# SCH_bottomBoard.net
KiCad netlist of a schematic drawn in EasyEDA
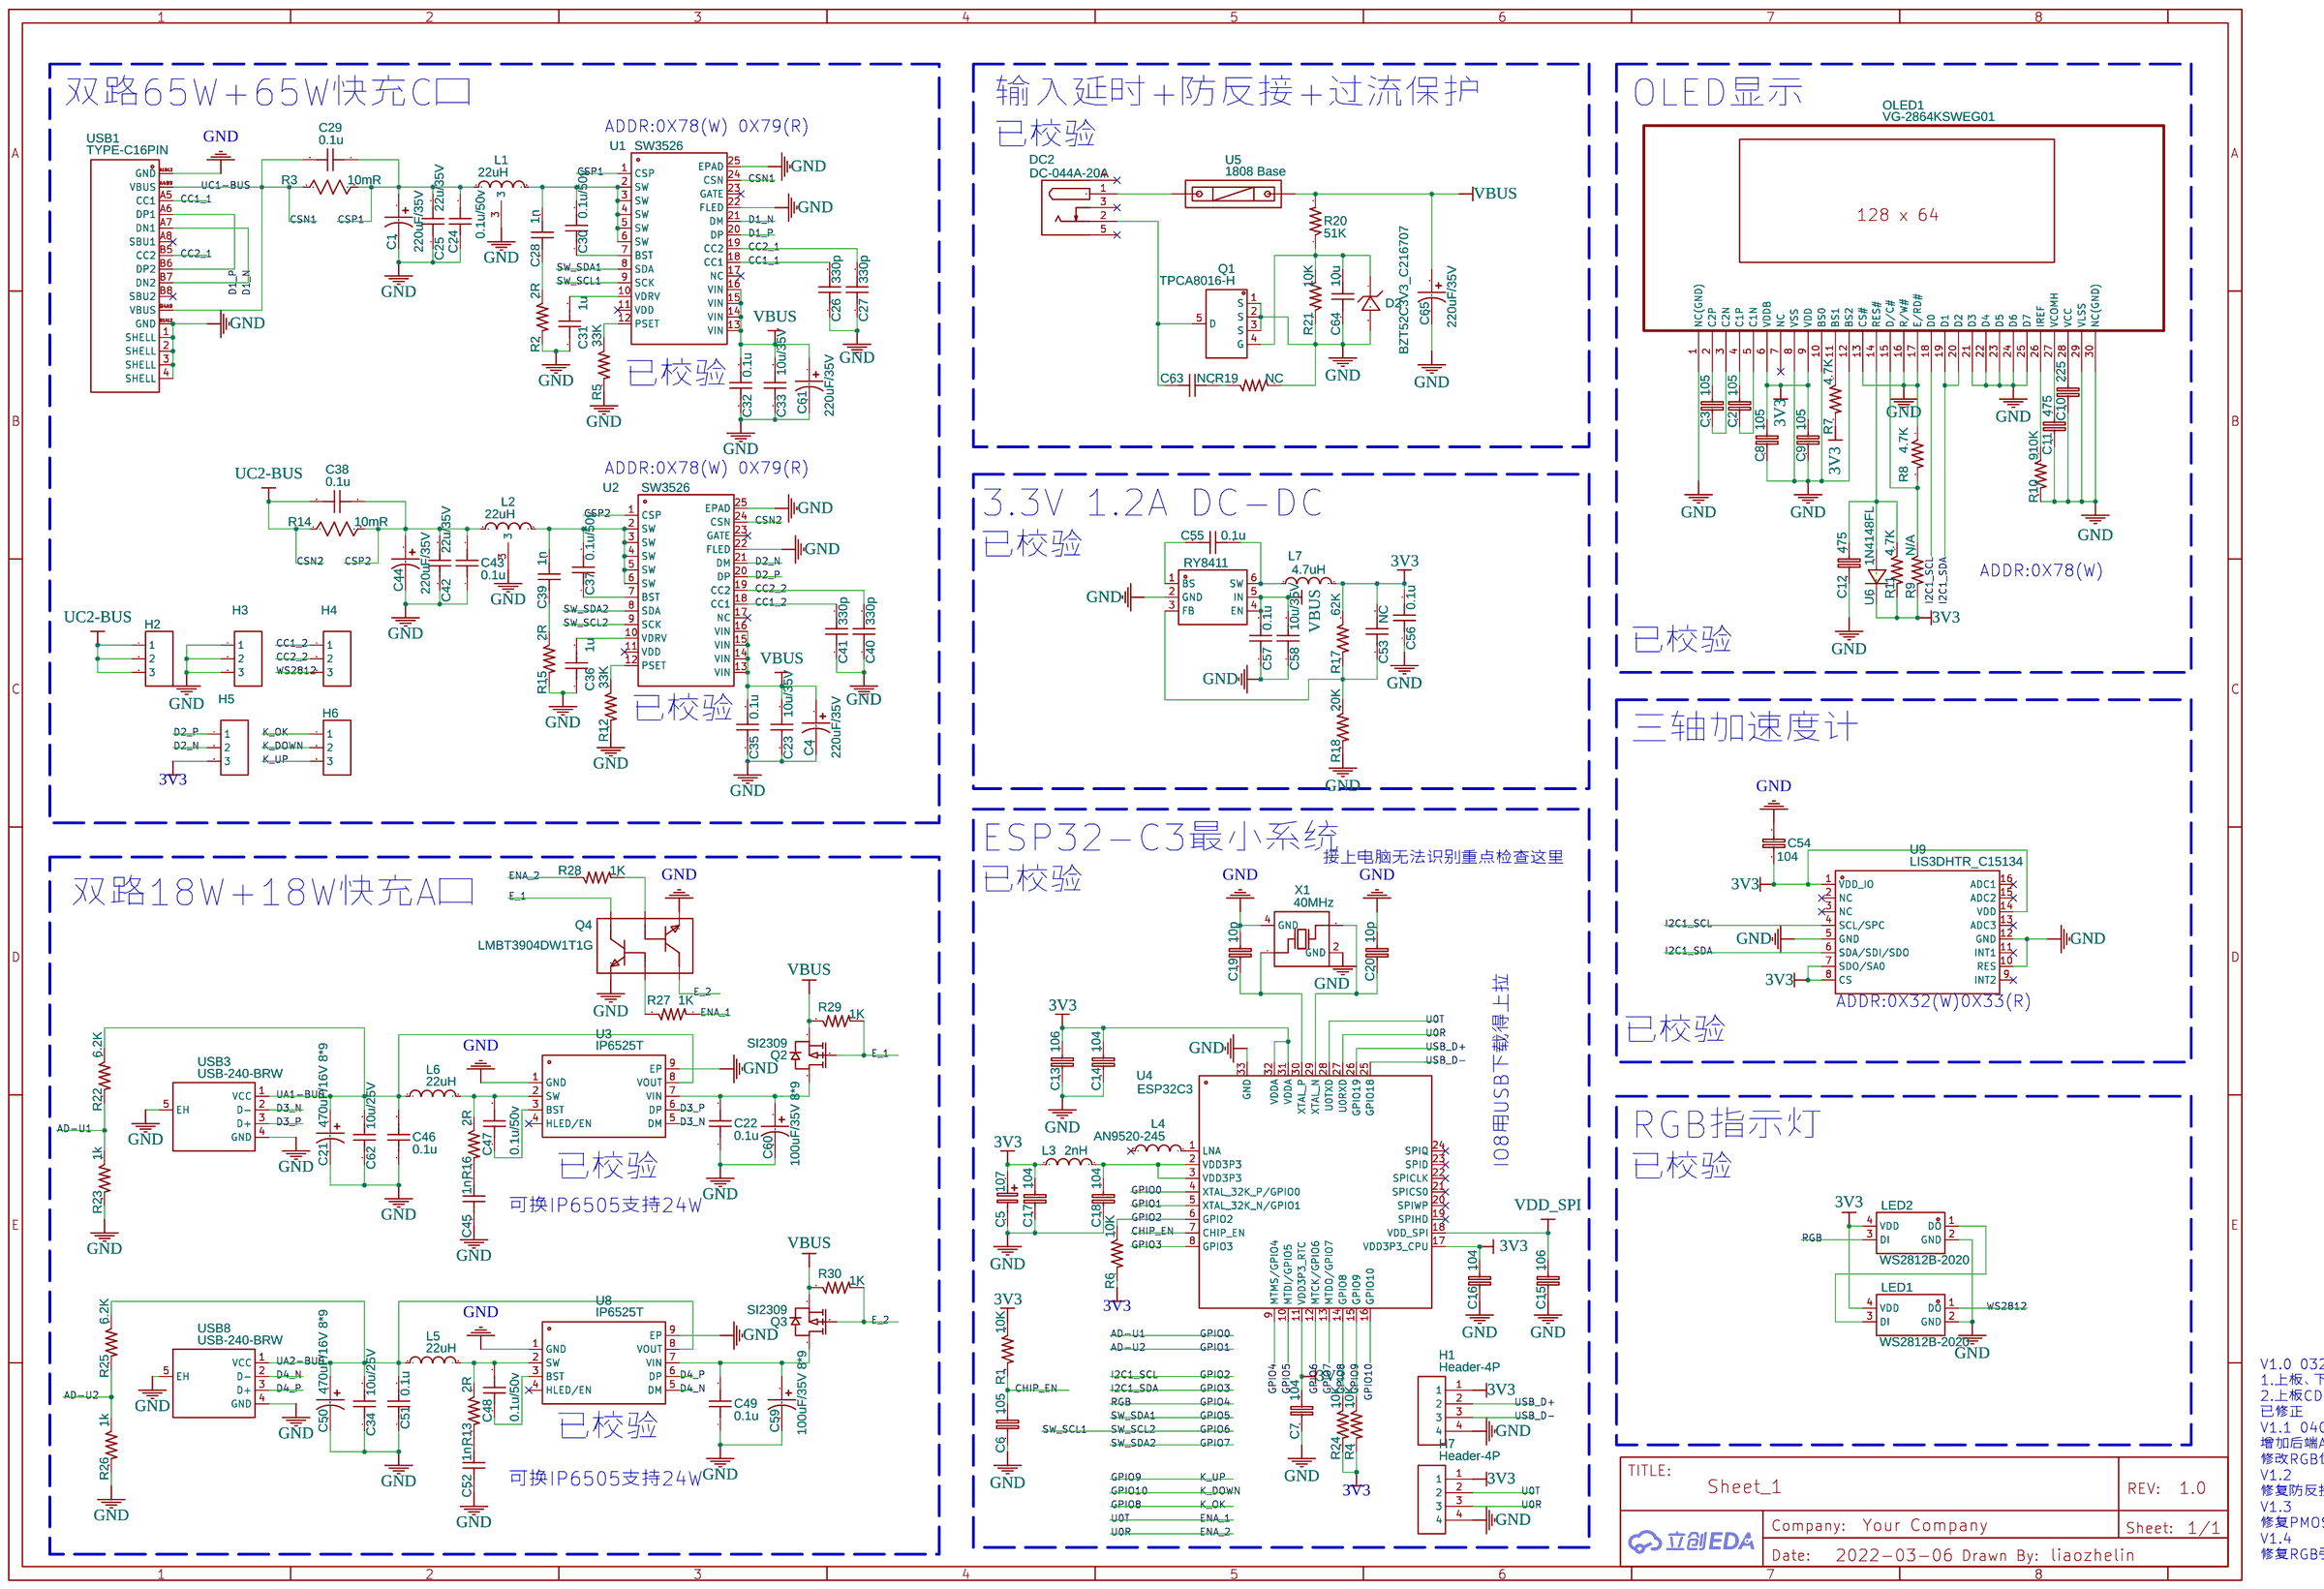
[diagram p0: schematic sheet]

(export (version "E")
  (design (tool "Eeschema 10.0.6"))
  (components
    (comp (ref "BS")
      (value "RY8411")
      (fields (field (name "BOM_Supplier Part") "C9900000347"))
      (libsource (lib "") (part "RY8411"))
    )
    (comp (ref "C1")
      (value "220uF/35V")
      (fields
        (field (name "BOM_Manufacturer Part") "BC016M821LO8*12L-1A4T")
        (field (name "BOM_Supplier Part") "C516110")
      )
      (libsource (lib "") (part "BC016M821LO8*12L-1A4T_1"))
    )
    (comp (ref "C2") (value "105") (libsource (lib "") (part "1.0PF-50V(-_+.25PF)(0603)")))
    (comp (ref "C3") (value "105") (libsource (lib "") (part "1.0PF-50V(-_+.25PF)(0603)")))
    (comp (ref "C4")
      (value "220uF/35V")
      (fields
        (field (name "BOM_Manufacturer Part") "BC016M821LO8*12L-1A4T")
        (field (name "BOM_Supplier Part") "C516110")
      )
      (libsource (lib "") (part "BC016M821LO8*12L-1A4T_1"))
    )
    (comp (ref "C5") (value "107") (libsource (lib "") (part "C_Tan_SMD_B_EU")))
    (comp (ref "C6") (value "105") (libsource (lib "") (part "1.0PF-50V(-_+.25PF)(0603)")))
    (comp (ref "C7") (value "104") (libsource (lib "") (part "1.0PF-50V(-_+.25PF)(0603)")))
    (comp (ref "C8") (value "105") (libsource (lib "") (part "1.0PF-50V(-_+.25PF)(0603)")))
    (comp (ref "C9") (value "105") (libsource (lib "") (part "1.0PF-50V(-_+.25PF)(0603)")))
    (comp (ref "C10") (value "225") (libsource (lib "") (part "1.0PF-50V(-_+.25PF)(0603)")))
    (comp (ref "C11") (value "475") (libsource (lib "") (part "1.0PF-50V(-_+.25PF)(0603)")))
    (comp (ref "C12") (value "475") (libsource (lib "") (part "1.0PF-50V(-_+.25PF)(0603)")))
    (comp (ref "C13") (value "106") (libsource (lib "") (part "1.0PF-50V(-_+.25PF)(0603)")))
    (comp (ref "C14") (value "104") (libsource (lib "") (part "1.0PF-50V(-_+.25PF)(0603)")))
    (comp (ref "C15") (value "106") (libsource (lib "") (part "1.0PF-50V(-_+.25PF)(0603)")))
    (comp (ref "C16") (value "104") (libsource (lib "") (part "1.0PF-50V(-_+.25PF)(0603)")))
    (comp (ref "C17") (value "104") (libsource (lib "") (part "1.0PF-50V(-_+.25PF)(0603)")))
    (comp (ref "C18") (value "104") (libsource (lib "") (part "1.0PF-50V(-_+.25PF)(0603)")))
    (comp (ref "C19") (value "10p") (libsource (lib "") (part "1.0PF-50V(-_+.25PF)(0603)")))
    (comp (ref "C20") (value "10p") (libsource (lib "") (part "1.0PF-50V(-_+.25PF)(0603)")))
    (comp (ref "C21")
      (value "470uF/16V 8*9")
      (fields
        (field (name "BOM_Manufacturer Part") "BC016M821LO8*12L-1A4T")
        (field (name "BOM_Supplier Part") "C516110")
      )
      (libsource (lib "") (part "BC016M821LO8*12L-1A4T_2"))
    )
    (comp (ref "C22") (value "0.1u") (libsource (lib "") (part "C_0805_US")))
    (comp (ref "C23") (value "10u/35V") (libsource (lib "") (part "C_0805_US")))
    (comp (ref "C24") (value "0.1u/50v") (libsource (lib "") (part "C_0805_US")))
    (comp (ref "C25") (value "22u/35V") (libsource (lib "") (part "C_0805_US")))
    (comp (ref "C26") (value "330p") (libsource (lib "") (part "C_0805_US")))
    (comp (ref "C27") (value "330p") (libsource (lib "") (part "C_0805_US")))
    (comp (ref "C28") (value "1n") (libsource (lib "") (part "C_0805_US")))
    (comp (ref "C29") (value "0.1u") (libsource (lib "") (part "C_0805_US_1")))
    (comp (ref "C30") (value "0.1u/50v") (libsource (lib "") (part "C_0805_US")))
    (comp (ref "C31") (value "1u") (libsource (lib "") (part "C_0805_US")))
    (comp (ref "C32") (value "0.1u") (libsource (lib "") (part "C_0805_US")))
    (comp (ref "C33") (value "10u/35V") (libsource (lib "") (part "C_0805_US")))
    (comp (ref "C34") (value "10u/25V") (libsource (lib "") (part "C_0805_US")))
    (comp (ref "C35") (value "0.1u") (libsource (lib "") (part "C_0805_US")))
    (comp (ref "C36") (value "1u") (libsource (lib "") (part "C_0805_US")))
    (comp (ref "C37") (value "0.1u/50v") (libsource (lib "") (part "C_0805_US")))
    (comp (ref "C38") (value "0.1u") (libsource (lib "") (part "C_0805_US_1")))
    (comp (ref "C39") (value "1n") (libsource (lib "") (part "C_0805_US")))
    (comp (ref "C40") (value "330p") (libsource (lib "") (part "C_0805_US")))
    (comp (ref "C41") (value "330p") (libsource (lib "") (part "C_0805_US")))
    (comp (ref "C42") (value "22u/35V") (libsource (lib "") (part "C_0805_US")))
    (comp (ref "C43") (value "0.1u") (libsource (lib "") (part "C_0805_US")))
    (comp (ref "C44")
      (value "220uF/35V")
      (fields
        (field (name "BOM_Manufacturer Part") "BC016M821LO8*12L-1A4T")
        (field (name "BOM_Supplier Part") "C516110")
      )
      (libsource (lib "") (part "BC016M821LO8*12L-1A4T_1"))
    )
    (comp (ref "C45") (value "1n") (libsource (lib "") (part "C_0805_US")))
    (comp (ref "C46") (value "0.1u") (libsource (lib "") (part "C_0805_US")))
    (comp (ref "C47") (value "0.1u/50v") (libsource (lib "") (part "C_0805_US")))
    (comp (ref "C48") (value "0.1u/50v") (libsource (lib "") (part "C_0805_US")))
    (comp (ref "C49") (value "0.1u") (libsource (lib "") (part "C_0805_US")))
    (comp (ref "C50")
      (value "470uF/16V 8*9")
      (fields
        (field (name "BOM_Manufacturer Part") "BC016M821LO8*12L-1A4T")
        (field (name "BOM_Supplier Part") "C516110")
      )
      (libsource (lib "") (part "BC016M821LO8*12L-1A4T_2"))
    )
    (comp (ref "C51") (value "0.1u") (libsource (lib "") (part "C_0805_US")))
    (comp (ref "C52") (value "1n") (libsource (lib "") (part "C_0805_US")))
    (comp (ref "C53") (value "NC") (libsource (lib "") (part "C_0805_US")))
    (comp (ref "C54") (value "104") (libsource (lib "") (part "1.0PF-50V(-_+.25PF)(0603)")))
    (comp (ref "C55") (value "0.1u") (libsource (lib "") (part "C_0805_US_1")))
    (comp (ref "C56") (value "0.1u") (libsource (lib "") (part "C_0805_US")))
    (comp (ref "C57") (value "0.1u") (libsource (lib "") (part "C_0805_US_2")))
    (comp (ref "C58") (value "10u/35V") (libsource (lib "") (part "C_0805_US")))
    (comp (ref "C59")
      (value "100uF/35V 8*9")
      (fields
        (field (name "BOM_Manufacturer Part") "BC016M821LO8*12L-1A4T")
        (field (name "BOM_Supplier Part") "C516110")
      )
      (libsource (lib "") (part "BC016M821LO8*12L-1A4T"))
    )
    (comp (ref "C60")
      (value "100uF/35V 8*9")
      (fields
        (field (name "BOM_Manufacturer Part") "BC016M821LO8*12L-1A4T")
        (field (name "BOM_Supplier Part") "C516110")
      )
      (libsource (lib "") (part "BC016M821LO8*12L-1A4T"))
    )
    (comp (ref "C61")
      (value "220uF/35V")
      (fields
        (field (name "BOM_Manufacturer Part") "BC016M821LO8*12L-1A4T")
        (field (name "BOM_Supplier Part") "C516110")
      )
      (libsource (lib "") (part "BC016M821LO8*12L-1A4T_1"))
    )
    (comp (ref "C62") (value "10u/25V") (libsource (lib "") (part "C_0805_US")))
    (comp (ref "C63") (value "NC") (libsource (lib "") (part "C_0805_US_1")))
    (comp (ref "C64") (value "10u") (libsource (lib "") (part "C_0805_US")))
    (comp (ref "C65")
      (value "220uF/35V")
      (fields
        (field (name "BOM_Manufacturer Part") "BC016M821LO8*12L-1A4T")
        (field (name "BOM_Supplier Part") "C516110")
      )
      (libsource (lib "") (part "BC016M821LO8*12L-1A4T_3"))
    )
    (comp (ref "D2")
      (value "BZT52C3V3_C216707")
      (fields (field (name "BOM_Manufacturer Part") "BZT52C3V3") (field (name "BOM_Supplier Part") "C216707"))
      (libsource (lib "") (part "BZT52C3V3_C216707"))
    )
    (comp (ref "DC2")
      (value "DC-044A-20A")
      (fields (field (name "BOM_Supplier Part") "C129006"))
      (libsource (lib "") (part "DC-044A-20A"))
    )
    (comp (ref "H1") (value "Header-4P") (libsource (lib "") (part "Header-4P")))
    (comp (ref "H2")
      (value "HDR-F-2.54_1x3")
      (fields (field (name "BOM_Supplier Part") "C146690"))
      (libsource (lib "") (part "HDR-F-2.54_1x3"))
    )
    (comp (ref "H3")
      (value "HDR-F-2.54_1x3")
      (fields (field (name "BOM_Supplier Part") "C146690"))
      (libsource (lib "") (part "HDR-F-2.54_1x3"))
    )
    (comp (ref "H4")
      (value "HDR-F-2.54_1x3")
      (fields (field (name "BOM_Supplier Part") "C146690"))
      (libsource (lib "") (part "HDR-F-2.54_1x3"))
    )
    (comp (ref "H5")
      (value "HDR-F-2.54_1x3")
      (fields (field (name "BOM_Supplier Part") "C146690"))
      (libsource (lib "") (part "HDR-F-2.54_1x3"))
    )
    (comp (ref "H6")
      (value "HDR-F-2.54_1x3")
      (fields (field (name "BOM_Supplier Part") "C146690"))
      (libsource (lib "") (part "HDR-F-2.54_1x3"))
    )
    (comp (ref "H7") (value "Header-4P") (libsource (lib "") (part "Header-4P")))
    (comp (ref "L1")
      (value "22uH")
      (fields
        (field (name "BOM_Manufacturer Part") "CDEP147NP-6R1MC-125")
        (field (name "BOM_Supplier Part") "C2455724")
      )
      (libsource (lib "") (part "CDEP147NP-6R1MC-125"))
    )
    (comp (ref "L2")
      (value "22uH")
      (fields
        (field (name "BOM_Manufacturer Part") "CDEP147NP-6R1MC-125")
        (field (name "BOM_Supplier Part") "C2455724")
      )
      (libsource (lib "") (part "CDEP147NP-6R1MC-125"))
    )
    (comp (ref "L3") (value "2nH") (libsource (lib "") (part "L0603_US")))
    (comp (ref "L4")
      (value "AN9520-245")
      (fields (field (name "BOM_Supplier Part") "C99665"))
      (libsource (lib "") (part "AN9520-245"))
    )
    (comp (ref "L5")
      (value "22uH")
      (fields
        (field (name "BOM_Manufacturer Part") "CDRH127NP-470MC")
        (field (name "BOM_Supplier Part") "C167265")
      )
      (libsource (lib "") (part "CDRH127NP-470MC"))
    )
    (comp (ref "L6")
      (value "22uH")
      (fields
        (field (name "BOM_Manufacturer Part") "CDRH127NP-470MC")
        (field (name "BOM_Supplier Part") "C167265")
      )
      (libsource (lib "") (part "CDRH127NP-470MC"))
    )
    (comp (ref "L7")
      (value "4.7uH")
      (fields
        (field (name "BOM_Manufacturer Part") "CD43(L)-10uH")
        (field (name "BOM_Supplier Part") "C9900005836")
      )
      (libsource (lib "") (part "CD43(L)-10UH"))
    )
    (comp (ref "LED1")
      (value "WS2812B-2020")
      (fields (field (name "BOM_Supplier Part") "C965555"))
      (libsource (lib "") (part "WS2812B-2020"))
    )
    (comp (ref "LED2")
      (value "WS2812B-2020")
      (fields (field (name "BOM_Supplier Part") "C965555"))
      (libsource (lib "") (part "WS2812B-2020"))
    )
    (comp (ref "OLED1")
      (value "VG-2864KSWEG01")
      (fields (field (name "BOM_Supplier Part") "C194313"))
      (libsource (lib "") (part "VG-2864KSWEG01"))
    )
    (comp (ref "Q1")
      (value "TPCA8016-H")
      (fields (field (name "BOM_Supplier Part") "C37805"))
      (libsource (lib "") (part "TPCA8016-H"))
    )
    (comp (ref "Q2")
      (value "SI2309")
      (fields
        (field (name "BOM_Manufacturer Part") "SI2309CDS-T1-E3")
        (field (name "BOM_Supplier Part") "C553975")
      )
      (libsource (lib "") (part "SI2309CDS-T1-E3"))
    )
    (comp (ref "Q3")
      (value "SI2309")
      (fields
        (field (name "BOM_Manufacturer Part") "SI2309CDS-T1-E3")
        (field (name "BOM_Supplier Part") "C553975")
      )
      (libsource (lib "") (part "SI2309CDS-T1-E3_1"))
    )
    (comp (ref "Q4")
      (value "LMBT3904DW1T1G")
      (fields (field (name "BOM_Supplier Part") "C131781"))
      (libsource (lib "") (part "LMBT3904DW1T1G"))
    )
    (comp (ref "R1") (value "10K") (libsource (lib "") (part "1.2MOHMS-1_10W-1%(0603)_1")))
    (comp (ref "R2") (value "2R") (libsource (lib "") (part "1.2MOHMS-1_10W-1%(0603)_1")))
    (comp (ref "R3") (value "10mR") (libsource (lib "") (part "R_1206_US")))
    (comp (ref "R4") (value "10K") (libsource (lib "") (part "1.2MOHMS-1_10W-1%(0603)_1")))
    (comp (ref "R5") (value "33K") (libsource (lib "") (part "1.2MOHMS-1_10W-1%(0603)_1")))
    (comp (ref "R6") (value "10K") (libsource (lib "") (part "1.2MOHMS-1_10W-1%(0603)_1")))
    (comp (ref "R7") (value "4.7K") (libsource (lib "") (part "1.2MOHMS-1_10W-1%(0603)_1")))
    (comp (ref "R8") (value "4.7K") (libsource (lib "") (part "1.2MOHMS-1_10W-1%(0603)_1")))
    (comp (ref "R9") (value "N/A") (libsource (lib "") (part "1.2MOHMS-1_10W-1%(0603)_1")))
    (comp (ref "R10") (value "910K") (libsource (lib "") (part "1.2MOHMS-1_10W-1%(0603)_1")))
    (comp (ref "R11") (value "4.7K") (libsource (lib "") (part "1.2MOHMS-1_10W-1%(0603)_1")))
    (comp (ref "R12") (value "33K") (libsource (lib "") (part "1.2MOHMS-1_10W-1%(0603)_1")))
    (comp (ref "R13") (value "2R") (libsource (lib "") (part "1.2MOHMS-1_10W-1%(0603)_1")))
    (comp (ref "R14") (value "10mR") (libsource (lib "") (part "R_1206_US")))
    (comp (ref "R15") (value "2R") (libsource (lib "") (part "1.2MOHMS-1_10W-1%(0603)_1")))
    (comp (ref "R16") (value "2R") (libsource (lib "") (part "1.2MOHMS-1_10W-1%(0603)_1")))
    (comp (ref "R17") (value "62K") (libsource (lib "") (part "1.2MOHMS-1_10W-1%(0603)_1")))
    (comp (ref "R18") (value "20K") (libsource (lib "") (part "1.2MOHMS-1_10W-1%(0603)_1")))
    (comp (ref "R19") (value "NC") (libsource (lib "") (part "1.2MOHMS-1_10W-1%(0603)_2")))
    (comp (ref "R20") (value "51K") (libsource (lib "") (part "1.2MOHMS-1_10W-1%(0603)")))
    (comp (ref "R21") (value "10K") (libsource (lib "") (part "1.2MOHMS-1_10W-1%(0603)")))
    (comp (ref "R22") (value "6.2K") (libsource (lib "") (part "1.2MOHMS-1_10W-1%(0603)_1")))
    (comp (ref "R23") (value "1k") (libsource (lib "") (part "1.2MOHMS-1_10W-1%(0603)_1")))
    (comp (ref "R24") (value "10K") (libsource (lib "") (part "1.2MOHMS-1_10W-1%(0603)_1")))
    (comp (ref "R25") (value "6.2K") (libsource (lib "") (part "1.2MOHMS-1_10W-1%(0603)_1")))
    (comp (ref "R26") (value "1k") (libsource (lib "") (part "1.2MOHMS-1_10W-1%(0603)_1")))
    (comp (ref "R27") (value "1K") (libsource (lib "") (part "1.2MOHMS-1_10W-1%(0603)_2")))
    (comp (ref "R28") (value "1K") (libsource (lib "") (part "1.2MOHMS-1_10W-1%(0603)_2")))
    (comp (ref "R29") (value "1K") (libsource (lib "") (part "1.2MOHMS-1_10W-1%(0603)_2")))
    (comp (ref "R30") (value "1K") (libsource (lib "") (part "1.2MOHMS-1_10W-1%(0603)_2")))
    (comp (ref "U1")
      (value "SW3526")
      (fields (field (name "BOM_Supplier Part") "C2912236"))
      (libsource (lib "") (part "SW3526"))
    )
    (comp (ref "U2")
      (value "SW3526")
      (fields (field (name "BOM_Supplier Part") "C2912236"))
      (libsource (lib "") (part "SW3526"))
    )
    (comp (ref "U3")
      (value "IP6525T")
      (fields (field (name "BOM_Supplier Part") "C432573"))
      (libsource (lib "") (part "IP6525T"))
    )
    (comp (ref "U4")
      (value "ESP32C3")
      (fields (field (name "BOM_Supplier Part") "C77967"))
      (libsource (lib "") (part "ESP32C3"))
    )
    (comp (ref "U5")
      (value "1808 Base")
      (fields (field (name "BOM_Supplier Part") "C3133"))
      (libsource (lib "") (part "1808 Base"))
    )
    (comp (ref "U6")
      (value "1N4148FL")
      (fields (field (name "BOM_Supplier Part") "C2874197"))
      (libsource (lib "") (part "1N4148FL"))
    )
    (comp (ref "U8")
      (value "IP6525T")
      (fields (field (name "BOM_Supplier Part") "C432573"))
      (libsource (lib "") (part "IP6525T"))
    )
    (comp (ref "U9")
      (value "LIS3DHTR_C15134")
      (fields (field (name "BOM_Manufacturer Part") "LIS3DHTR") (field (name "BOM_Supplier Part") "C15134"))
      (libsource (lib "") (part "LIS3DHTR_C15134"))
    )
    (comp (ref "USB1")
      (value "TYPE-C16PIN")
      (fields (field (name "BOM_Supplier Part") "C393939"))
      (libsource (lib "") (part "TYPE-C16PIN"))
    )
    (comp (ref "USB3")
      (value "USB-240-BRW")
      (fields (field (name "BOM_Supplier Part") "C720530"))
      (libsource (lib "") (part "USB-240-BRW"))
    )
    (comp (ref "USB8")
      (value "USB-240-BRW")
      (fields (field (name "BOM_Supplier Part") "C720530"))
      (libsource (lib "") (part "USB-240-BRW"))
    )
    (comp (ref "X1")
      (value "40MHz")
      (fields
        (field (name "BOM_Manufacturer Part") "SX32Y040000BF1T")
        (field (name "BOM_Supplier Part") "C271642")
      )
      (libsource (lib "") (part "SX32Y040000BF1T"))
    )
  )
  (nets
    (net (code "1") (name "/AD-U1") (class "Default")
      (node (ref "R22") (pin "2") (pinfunction "2_2") (pintype "unspecified"))
      (node (ref "R23") (pin "1") (pinfunction "1_1") (pintype "unspecified"))
      (node (ref "U4") (pin "4") (pinfunction "XTAL_32K_P/GPIO0_4") (pintype "unspecified"))
    )
    (net (code "2") (name "/AD-U2") (class "Default")
      (node (ref "R25") (pin "2") (pinfunction "2_2") (pintype "unspecified"))
      (node (ref "R26") (pin "1") (pinfunction "1_1") (pintype "unspecified"))
      (node (ref "U4") (pin "5") (pinfunction "XTAL_32K_N/GPIO1_5") (pintype "unspecified"))
    )
    (net (code "3") (name "/CC1_1") (class "Default")
      (node (ref "C26") (pin "2") (pinfunction "2_2") (pintype "unspecified"))
      (node (ref "U1") (pin "18") (pinfunction "CC1_18") (pintype "unspecified"))
      (node (ref "USB1") (pin "A5") (pinfunction "CC1_A5") (pintype "unspecified"))
    )
    (net (code "4") (name "/CC1_2") (class "Default")
      (node (ref "C41") (pin "2") (pinfunction "2_2") (pintype "unspecified"))
      (node (ref "H4") (pin "1") (pinfunction "1_1") (pintype "input"))
      (node (ref "U2") (pin "18") (pinfunction "CC1_18") (pintype "unspecified"))
    )
    (net (code "5") (name "/CC2_1") (class "Default")
      (node (ref "C27") (pin "2") (pinfunction "2_2") (pintype "unspecified"))
      (node (ref "U1") (pin "19") (pinfunction "CC2_19") (pintype "unspecified"))
      (node (ref "USB1") (pin "B5") (pinfunction "CC2_B5") (pintype "unspecified"))
    )
    (net (code "6") (name "/CC2_2") (class "Default")
      (node (ref "C40") (pin "2") (pinfunction "2_2") (pintype "unspecified"))
      (node (ref "H4") (pin "2") (pinfunction "2_2") (pintype "input"))
      (node (ref "U2") (pin "19") (pinfunction "CC2_19") (pintype "unspecified"))
    )
    (net (code "7") (name "/CHIP_EN") (class "Default")
      (node (ref "C6") (pin "1") (pinfunction "1_1") (pintype "unspecified"))
      (node (ref "R1") (pin "2") (pinfunction "2_2") (pintype "unspecified"))
      (node (ref "U4") (pin "7") (pinfunction "CHIP_EN_7") (pintype "unspecified"))
    )
    (net (code "8") (name "/CSN1") (class "Default")
      (node (ref "C29") (pin "2") (pinfunction "2_2") (pintype "unspecified"))
      (node (ref "R3") (pin "1") (pinfunction "1_1") (pintype "unspecified"))
      (node (ref "U1") (pin "24") (pinfunction "CSN_24") (pintype "unspecified"))
      (node (ref "USB1") (pin "A4B9") (pinfunction "VBUS_A4B9") (pintype "unspecified"))
      (node (ref "USB1") (pin "B4A9") (pinfunction "VBUS_B4A9") (pintype "unspecified"))
    )
    (net (code "9") (name "/CSP1") (class "Default")
      (node (ref "C1") (pin "1") (pinfunction "1_1") (pintype "unspecified"))
      (node (ref "C24") (pin "2") (pinfunction "2_2") (pintype "unspecified"))
      (node (ref "C25") (pin "2") (pinfunction "2_2") (pintype "unspecified"))
      (node (ref "C29") (pin "1") (pinfunction "1_1") (pintype "unspecified"))
      (node (ref "L1") (pin "2") (pinfunction "2_2") (pintype "unspecified"))
      (node (ref "R3") (pin "2") (pinfunction "2_2") (pintype "unspecified"))
      (node (ref "U1") (pin "1") (pinfunction "CSP_1") (pintype "unspecified"))
    )
    (net (code "10") (name "/CSP2") (class "Default")
      (node (ref "C38") (pin "1") (pinfunction "1_1") (pintype "unspecified"))
      (node (ref "C42") (pin "2") (pinfunction "2_2") (pintype "unspecified"))
      (node (ref "C43") (pin "2") (pinfunction "2_2") (pintype "unspecified"))
      (node (ref "C44") (pin "1") (pinfunction "1_1") (pintype "unspecified"))
      (node (ref "L2") (pin "2") (pinfunction "2_2") (pintype "unspecified"))
      (node (ref "R14") (pin "2") (pinfunction "2_2") (pintype "unspecified"))
      (node (ref "U2") (pin "1") (pinfunction "CSP_1") (pintype "unspecified"))
    )
    (net (code "11") (name "/D1_N") (class "Default")
      (node (ref "U1") (pin "21") (pinfunction "DM_21") (pintype "unspecified"))
      (node (ref "USB1") (pin "A7") (pinfunction "DN1_A7") (pintype "unspecified"))
      (node (ref "USB1") (pin "B7") (pinfunction "DN2_B7") (pintype "unspecified"))
    )
    (net (code "12") (name "/D1_P") (class "Default")
      (node (ref "U1") (pin "20") (pinfunction "DP_20") (pintype "unspecified"))
      (node (ref "USB1") (pin "A6") (pinfunction "DP1_A6") (pintype "unspecified"))
      (node (ref "USB1") (pin "B6") (pinfunction "DP2_B6") (pintype "unspecified"))
    )
    (net (code "13") (name "/D2_N") (class "Default")
      (node (ref "H5") (pin "2") (pinfunction "2_2") (pintype "input"))
      (node (ref "U2") (pin "21") (pinfunction "DM_21") (pintype "unspecified"))
    )
    (net (code "14") (name "/D2_P") (class "Default")
      (node (ref "H5") (pin "1") (pinfunction "1_1") (pintype "input"))
      (node (ref "U2") (pin "20") (pinfunction "DP_20") (pintype "unspecified"))
    )
    (net (code "15") (name "/D3_N") (class "Default")
      (node (ref "U3") (pin "5") (pinfunction "DM_5") (pintype "unspecified"))
      (node (ref "USB3") (pin "2") (pinfunction "D-_2") (pintype "input"))
    )
    (net (code "16") (name "/D3_P") (class "Default")
      (node (ref "U3") (pin "6") (pinfunction "DP_6") (pintype "unspecified"))
      (node (ref "USB3") (pin "3") (pinfunction "D+_3") (pintype "input"))
    )
    (net (code "17") (name "/D4_N") (class "Default")
      (node (ref "U8") (pin "5") (pinfunction "DM_5") (pintype "unspecified"))
      (node (ref "USB8") (pin "2") (pinfunction "D-_2") (pintype "input"))
    )
    (net (code "18") (name "/D4_P") (class "Default")
      (node (ref "U8") (pin "6") (pinfunction "DP_6") (pintype "unspecified"))
      (node (ref "USB8") (pin "3") (pinfunction "D+_3") (pintype "input"))
    )
    (net (code "19") (name "/ENA_1") (class "Default")
      (node (ref "H7") (pin "2") (pinfunction "2_2") (pintype "unspecified"))
      (node (ref "R27") (pin "2") (pinfunction "2_2") (pintype "unspecified"))
      (node (ref "U4") (pin "28") (pinfunction "U0TXD_28") (pintype "unspecified"))
    )
    (net (code "20") (name "/ENA_2") (class "Default")
      (node (ref "H7") (pin "3") (pinfunction "3_3") (pintype "unspecified"))
      (node (ref "R28") (pin "1") (pinfunction "1_1") (pintype "unspecified"))
      (node (ref "U4") (pin "27") (pinfunction "U0RXD_27") (pintype "unspecified"))
    )
    (net (code "21") (name "/E_1") (class "Default")
      (node (ref "Q2") (pin "1") (pinfunction "G_1") (pintype "unspecified"))
      (node (ref "Q4") (pin "6") (pinfunction "C_6") (pintype "unspecified"))
      (node (ref "R29") (pin "2") (pinfunction "2_2") (pintype "unspecified"))
    )
    (net (code "22") (name "/E_2") (class "Default")
      (node (ref "Q3") (pin "1") (pinfunction "G_1") (pintype "unspecified"))
      (node (ref "Q4") (pin "3") (pinfunction "C_3") (pintype "unspecified"))
      (node (ref "R30") (pin "2") (pinfunction "2_2") (pintype "unspecified"))
    )
    (net (code "23") (name "/GPIO2") (class "Default")
      (node (ref "OLED1") (pin "18") (pinfunction "D0_18") (pintype "passive"))
      (node (ref "R6") (pin "1") (pinfunction "1_1") (pintype "unspecified"))
      (node (ref "U4") (pin "6") (pinfunction "GPIO2_6") (pintype "unspecified"))
      (node (ref "U9") (pin "4") (pinfunction "SCL/SPC_4") (pintype "unspecified"))
    )
    (net (code "24") (name "/GPIO3") (class "Default")
      (node (ref "OLED1") (pin "19") (pinfunction "D1_19") (pintype "passive"))
      (node (ref "OLED1") (pin "20") (pinfunction "D2_20") (pintype "passive"))
      (node (ref "U4") (pin "8") (pinfunction "GPIO3_8") (pintype "unspecified"))
      (node (ref "U9") (pin "6") (pinfunction "SDA/SDI/SDO_6") (pintype "unspecified"))
    )
    (net (code "25") (name "/GPIO4") (class "Default")
      (node (ref "LED2") (pin "3") (pinfunction "DI_3") (pintype "unspecified"))
      (node (ref "U4") (pin "9") (pinfunction "MTMS/GPIO4_9") (pintype "unspecified"))
    )
    (net (code "26") (name "/GPIO5") (class "Default")
      (node (ref "U1") (pin "8") (pinfunction "SDA_8") (pintype "unspecified"))
      (node (ref "U4") (pin "10") (pinfunction "MTDI/GPIO5_10") (pintype "unspecified"))
    )
    (net (code "27") (name "/GPIO6") (class "Default")
      (node (ref "U1") (pin "9") (pinfunction "SCK_9") (pintype "unspecified"))
      (node (ref "U2") (pin "9") (pinfunction "SCK_9") (pintype "unspecified"))
      (node (ref "U4") (pin "12") (pinfunction "MTCK/GPIO6_12") (pintype "unspecified"))
    )
    (net (code "28") (name "/GPIO7") (class "Default")
      (node (ref "U2") (pin "8") (pinfunction "SDA_8") (pintype "unspecified"))
      (node (ref "U4") (pin "13") (pinfunction "MTDO/GPIO7_13") (pintype "unspecified"))
    )
    (net (code "29") (name "/GPIO8") (class "Default")
      (node (ref "H6") (pin "1") (pinfunction "1_1") (pintype "input"))
      (node (ref "R24") (pin "1") (pinfunction "1_1") (pintype "unspecified"))
      (node (ref "U4") (pin "14") (pinfunction "GPIO8_14") (pintype "unspecified"))
    )
    (net (code "30") (name "/GPIO9") (class "Default")
      (node (ref "H6") (pin "3") (pinfunction "3_3") (pintype "input"))
      (node (ref "R4") (pin "1") (pinfunction "1_1") (pintype "unspecified"))
      (node (ref "U4") (pin "15") (pinfunction "GPIO9_15") (pintype "unspecified"))
    )
    (net (code "31") (name "/GPIO10") (class "Default")
      (node (ref "H6") (pin "2") (pinfunction "2_2") (pintype "input"))
      (node (ref "U4") (pin "16") (pinfunction "GPIO10_16") (pintype "unspecified"))
    )
    (net (code "32") (name "/UA1-BUS") (class "Default")
      (node (ref "C21") (pin "1") (pinfunction "1_1") (pintype "unspecified"))
      (node (ref "C46") (pin "2") (pinfunction "2_2") (pintype "unspecified"))
      (node (ref "C62") (pin "2") (pinfunction "2_2") (pintype "unspecified"))
      (node (ref "L6") (pin "1") (pinfunction "1_1") (pintype "unspecified"))
      (node (ref "R22") (pin "1") (pinfunction "1_1") (pintype "unspecified"))
      (node (ref "U3") (pin "8") (pinfunction "VOUT_8") (pintype "unspecified"))
      (node (ref "USB3") (pin "1") (pinfunction "VCC_1") (pintype "input"))
    )
    (net (code "33") (name "/UA2-BUS") (class "Default")
      (node (ref "C34") (pin "2") (pinfunction "2_2") (pintype "unspecified"))
      (node (ref "C50") (pin "1") (pinfunction "1_1") (pintype "unspecified"))
      (node (ref "C51") (pin "2") (pinfunction "2_2") (pintype "unspecified"))
      (node (ref "L5") (pin "1") (pinfunction "1_1") (pintype "unspecified"))
      (node (ref "R25") (pin "1") (pinfunction "1_1") (pintype "unspecified"))
      (node (ref "U8") (pin "8") (pinfunction "VOUT_8") (pintype "unspecified"))
      (node (ref "USB8") (pin "1") (pinfunction "VCC_1") (pintype "input"))
    )
    (net (code "34") (name "/USB_D+") (class "Default")
      (node (ref "H1") (pin "2") (pinfunction "2_2") (pintype "unspecified"))
      (node (ref "U4") (pin "26") (pinfunction "GPIO19_26") (pintype "unspecified"))
    )
    (net (code "35") (name "/USB_D-") (class "Default")
      (node (ref "H1") (pin "3") (pinfunction "3_3") (pintype "unspecified"))
      (node (ref "U4") (pin "25") (pinfunction "GPIO18_25") (pintype "unspecified"))
    )
    (net (code "36") (name "/WS2812") (class "Default")
      (node (ref "H4") (pin "3") (pinfunction "3_3") (pintype "input"))
      (node (ref "LED1") (pin "1") (pinfunction "DO_1") (pintype "unspecified"))
    )
    (net (code "37") (name "3V3") (class "Default")
      (node (ref "C13") (pin "1") (pinfunction "1_1") (pintype "unspecified"))
      (node (ref "C14") (pin "1") (pinfunction "1_1") (pintype "unspecified"))
      (node (ref "C16") (pin "1") (pinfunction "1_1") (pintype "unspecified"))
      (node (ref "C17") (pin "1") (pinfunction "1_1") (pintype "unspecified"))
      (node (ref "C5") (pin "1") (pinfunction "1_1") (pintype "unspecified"))
      (node (ref "C53") (pin "2") (pinfunction "2_2") (pintype "unspecified"))
      (node (ref "C54") (pin "2") (pinfunction "2_2") (pintype "unspecified"))
      (node (ref "C56") (pin "2") (pinfunction "2_2") (pintype "unspecified"))
      (node (ref "C7") (pin "1") (pinfunction "1_1") (pintype "unspecified"))
      (node (ref "C8") (pin "1") (pinfunction "1_1") (pintype "unspecified"))
      (node (ref "C9") (pin "1") (pinfunction "1_1") (pintype "unspecified"))
      (node (ref "H1") (pin "1") (pinfunction "1_1") (pintype "unspecified"))
      (node (ref "H5") (pin "3") (pinfunction "3_3") (pintype "input"))
      (node (ref "H7") (pin "1") (pinfunction "1_1") (pintype "unspecified"))
      (node (ref "L3") (pin "1") (pinfunction "1_1") (pintype "unspecified"))
      (node (ref "L7") (pin "2") (pinfunction "2_2") (pintype "unspecified"))
      (node (ref "LED1") (pin "4") (pinfunction "VDD_4") (pintype "unspecified"))
      (node (ref "LED2") (pin "4") (pinfunction "VDD_4") (pintype "unspecified"))
      (node (ref "OLED1") (pin "6") (pinfunction "VDDB_6") (pintype "passive"))
      (node (ref "OLED1") (pin "9") (pinfunction "VDD_9") (pintype "passive"))
      (node (ref "R1") (pin "1") (pinfunction "1_1") (pintype "unspecified"))
      (node (ref "R11") (pin "2") (pinfunction "2_2") (pintype "unspecified"))
      (node (ref "R17") (pin "1") (pinfunction "1_1") (pintype "unspecified"))
      (node (ref "R24") (pin "2") (pinfunction "2_2") (pintype "unspecified"))
      (node (ref "R4") (pin "2") (pinfunction "2_2") (pintype "unspecified"))
      (node (ref "R6") (pin "2") (pinfunction "2_2") (pintype "unspecified"))
      (node (ref "R7") (pin "2") (pinfunction "2_2") (pintype "unspecified"))
      (node (ref "R9") (pin "2") (pinfunction "2_2") (pintype "unspecified"))
      (node (ref "U4") (pin "11") (pinfunction "VDD3P3_RTC_11") (pintype "unspecified"))
      (node (ref "U4") (pin "17") (pinfunction "VDD3P3_CPU_17") (pintype "unspecified"))
      (node (ref "U4") (pin "31") (pinfunction "VDDA_31") (pintype "unspecified"))
      (node (ref "U4") (pin "32") (pinfunction "VDDA_32") (pintype "unspecified"))
      (node (ref "U6") (pin "1") (pinfunction "C_1") (pintype "unspecified"))
      (node (ref "U9") (pin "1") (pinfunction "VDD_IO_1") (pintype "unspecified"))
      (node (ref "U9") (pin "14") (pinfunction "VDD_14") (pintype "unspecified"))
      (node (ref "U9") (pin "7") (pinfunction "SDO/SA0_7") (pintype "unspecified"))
      (node (ref "U9") (pin "8") (pinfunction "CS_8") (pintype "unspecified"))
    )
    (net (code "38") (name "GND") (class "Default")
      (node (ref "BS") (pin "2") (pinfunction "GND_2") (pintype "unspecified"))
      (node (ref "C1") (pin "2") (pinfunction "2_2") (pintype "unspecified"))
      (node (ref "C10") (pin "2") (pinfunction "2_2") (pintype "unspecified"))
      (node (ref "C11") (pin "2") (pinfunction "2_2") (pintype "unspecified"))
      (node (ref "C12") (pin "2") (pinfunction "2_2") (pintype "unspecified"))
      (node (ref "C13") (pin "2") (pinfunction "2_2") (pintype "unspecified"))
      (node (ref "C14") (pin "2") (pinfunction "2_2") (pintype "unspecified"))
      (node (ref "C15") (pin "2") (pinfunction "2_2") (pintype "unspecified"))
      (node (ref "C16") (pin "2") (pinfunction "2_2") (pintype "unspecified"))
      (node (ref "C17") (pin "2") (pinfunction "2_2") (pintype "unspecified"))
      (node (ref "C18") (pin "2") (pinfunction "2_2") (pintype "unspecified"))
      (node (ref "C19") (pin "1") (pinfunction "1_1") (pintype "unspecified"))
      (node (ref "C20") (pin "1") (pinfunction "1_1") (pintype "unspecified"))
      (node (ref "C21") (pin "2") (pinfunction "2_2") (pintype "unspecified"))
      (node (ref "C22") (pin "1") (pinfunction "1_1") (pintype "unspecified"))
      (node (ref "C23") (pin "1") (pinfunction "1_1") (pintype "unspecified"))
      (node (ref "C24") (pin "1") (pinfunction "1_1") (pintype "unspecified"))
      (node (ref "C25") (pin "1") (pinfunction "1_1") (pintype "unspecified"))
      (node (ref "C26") (pin "1") (pinfunction "1_1") (pintype "unspecified"))
      (node (ref "C27") (pin "1") (pinfunction "1_1") (pintype "unspecified"))
      (node (ref "C31") (pin "1") (pinfunction "1_1") (pintype "unspecified"))
      (node (ref "C32") (pin "1") (pinfunction "1_1") (pintype "unspecified"))
      (node (ref "C33") (pin "1") (pinfunction "1_1") (pintype "unspecified"))
      (node (ref "C34") (pin "1") (pinfunction "1_1") (pintype "unspecified"))
      (node (ref "C35") (pin "1") (pinfunction "1_1") (pintype "unspecified"))
      (node (ref "C36") (pin "1") (pinfunction "1_1") (pintype "unspecified"))
      (node (ref "C4") (pin "2") (pinfunction "2_2") (pintype "unspecified"))
      (node (ref "C40") (pin "1") (pinfunction "1_1") (pintype "unspecified"))
      (node (ref "C41") (pin "1") (pinfunction "1_1") (pintype "unspecified"))
      (node (ref "C42") (pin "1") (pinfunction "1_1") (pintype "unspecified"))
      (node (ref "C43") (pin "1") (pinfunction "1_1") (pintype "unspecified"))
      (node (ref "C44") (pin "2") (pinfunction "2_2") (pintype "unspecified"))
      (node (ref "C45") (pin "1") (pinfunction "1_1") (pintype "unspecified"))
      (node (ref "C46") (pin "1") (pinfunction "1_1") (pintype "unspecified"))
      (node (ref "C49") (pin "1") (pinfunction "1_1") (pintype "unspecified"))
      (node (ref "C5") (pin "2") (pinfunction "2_2") (pintype "unspecified"))
      (node (ref "C50") (pin "2") (pinfunction "2_2") (pintype "unspecified"))
      (node (ref "C51") (pin "1") (pinfunction "1_1") (pintype "unspecified"))
      (node (ref "C52") (pin "1") (pinfunction "1_1") (pintype "unspecified"))
      (node (ref "C54") (pin "1") (pinfunction "1_1") (pintype "unspecified"))
      (node (ref "C56") (pin "1") (pinfunction "1_1") (pintype "unspecified"))
      (node (ref "C57") (pin "2") (pinfunction "2_2") (pintype "unspecified"))
      (node (ref "C58") (pin "1") (pinfunction "1_1") (pintype "unspecified"))
      (node (ref "C59") (pin "2") (pinfunction "2_2") (pintype "unspecified"))
      (node (ref "C6") (pin "2") (pinfunction "2_2") (pintype "unspecified"))
      (node (ref "C60") (pin "2") (pinfunction "2_2") (pintype "unspecified"))
      (node (ref "C61") (pin "2") (pinfunction "2_2") (pintype "unspecified"))
      (node (ref "C62") (pin "1") (pinfunction "1_1") (pintype "unspecified"))
      (node (ref "C64") (pin "1") (pinfunction "1_1") (pintype "unspecified"))
      (node (ref "C65") (pin "2") (pinfunction "2_2") (pintype "unspecified"))
      (node (ref "C7") (pin "2") (pinfunction "2_2") (pintype "unspecified"))
      (node (ref "C8") (pin "2") (pinfunction "2_2") (pintype "unspecified"))
      (node (ref "C9") (pin "2") (pinfunction "2_2") (pintype "unspecified"))
      (node (ref "D2") (pin "2") (pinfunction "2_2") (pintype "unspecified"))
      (node (ref "H1") (pin "4") (pinfunction "4_4") (pintype "unspecified"))
      (node (ref "H3") (pin "1") (pinfunction "1_1") (pintype "input"))
      (node (ref "H3") (pin "2") (pinfunction "2_2") (pintype "input"))
      (node (ref "H3") (pin "3") (pinfunction "3_3") (pintype "input"))
      (node (ref "H7") (pin "4") (pinfunction "4_4") (pintype "unspecified"))
      (node (ref "L1") (pin "3") (pinfunction "3_3") (pintype "unspecified"))
      (node (ref "L2") (pin "3") (pinfunction "3_3") (pintype "unspecified"))
      (node (ref "LED1") (pin "2") (pinfunction "GND_2") (pintype "unspecified"))
      (node (ref "LED2") (pin "2") (pinfunction "GND_2") (pintype "unspecified"))
      (node (ref "OLED1") (pin "1") (pinfunction "NC(GND)_1") (pintype "passive"))
      (node (ref "OLED1") (pin "10") (pinfunction "BS0_10") (pintype "passive"))
      (node (ref "OLED1") (pin "12") (pinfunction "BS2_12") (pintype "passive"))
      (node (ref "OLED1") (pin "13") (pinfunction "CS#_13") (pintype "passive"))
      (node (ref "OLED1") (pin "16") (pinfunction "R/W#_16") (pintype "passive"))
      (node (ref "OLED1") (pin "17") (pinfunction "E/RD#_17") (pintype "passive"))
      (node (ref "OLED1") (pin "21") (pinfunction "D3_21") (pintype "passive"))
      (node (ref "OLED1") (pin "22") (pinfunction "D4_22") (pintype "passive"))
      (node (ref "OLED1") (pin "23") (pinfunction "D5_23") (pintype "passive"))
      (node (ref "OLED1") (pin "24") (pinfunction "D6_24") (pintype "passive"))
      (node (ref "OLED1") (pin "25") (pinfunction "D7_25") (pintype "passive"))
      (node (ref "OLED1") (pin "29") (pinfunction "VLSS_29") (pintype "passive"))
      (node (ref "OLED1") (pin "30") (pinfunction "NC(GND)_30") (pintype "passive"))
      (node (ref "OLED1") (pin "8") (pinfunction "VSS_8") (pintype "passive"))
      (node (ref "Q1") (pin "1") (pinfunction "S_1") (pintype "unspecified"))
      (node (ref "Q1") (pin "2") (pinfunction "S_2") (pintype "unspecified"))
      (node (ref "Q1") (pin "3") (pinfunction "S_3") (pintype "unspecified"))
      (node (ref "Q4") (pin "1") (pinfunction "E_1") (pintype "unspecified"))
      (node (ref "Q4") (pin "4") (pinfunction "E_4") (pintype "unspecified"))
      (node (ref "R10") (pin "2") (pinfunction "2_2") (pintype "unspecified"))
      (node (ref "R12") (pin "2") (pinfunction "2_2") (pintype "unspecified"))
      (node (ref "R15") (pin "2") (pinfunction "2_2") (pintype "unspecified"))
      (node (ref "R18") (pin "2") (pinfunction "2_2") (pintype "unspecified"))
      (node (ref "R19") (pin "2") (pinfunction "2_2") (pintype "unspecified"))
      (node (ref "R2") (pin "2") (pinfunction "2_2") (pintype "unspecified"))
      (node (ref "R21") (pin "1") (pinfunction "1_1") (pintype "unspecified"))
      (node (ref "R23") (pin "2") (pinfunction "2_2") (pintype "unspecified"))
      (node (ref "R26") (pin "2") (pinfunction "2_2") (pintype "unspecified"))
      (node (ref "R5") (pin "2") (pinfunction "2_2") (pintype "unspecified"))
      (node (ref "R8") (pin "1") (pinfunction "1_1") (pintype "unspecified"))
      (node (ref "U1") (pin "22") (pinfunction "FLED_22") (pintype "unspecified"))
      (node (ref "U1") (pin "25") (pinfunction "EPAD_25") (pintype "unspecified"))
      (node (ref "U2") (pin "22") (pinfunction "FLED_22") (pintype "unspecified"))
      (node (ref "U2") (pin "25") (pinfunction "EPAD_25") (pintype "unspecified"))
      (node (ref "U3") (pin "1") (pinfunction "GND_1") (pintype "unspecified"))
      (node (ref "U3") (pin "9") (pinfunction "EP_9") (pintype "unspecified"))
      (node (ref "U4") (pin "33") (pinfunction "GND_33") (pintype "unspecified"))
      (node (ref "U8") (pin "1") (pinfunction "GND_1") (pintype "unspecified"))
      (node (ref "U8") (pin "9") (pinfunction "EP_9") (pintype "unspecified"))
      (node (ref "U9") (pin "10") (pinfunction "RES_10") (pintype "unspecified"))
      (node (ref "U9") (pin "12") (pinfunction "GND_12") (pintype "unspecified"))
      (node (ref "U9") (pin "5") (pinfunction "GND_5") (pintype "unspecified"))
      (node (ref "USB1") (pin "1") (pinfunction "SHELL_1") (pintype "unspecified"))
      (node (ref "USB1") (pin "2") (pinfunction "SHELL_2") (pintype "unspecified"))
      (node (ref "USB1") (pin "3") (pinfunction "SHELL_3") (pintype "unspecified"))
      (node (ref "USB1") (pin "4") (pinfunction "SHELL_4") (pintype "unspecified"))
      (node (ref "USB1") (pin "A1B12") (pinfunction "GND_A1B12") (pintype "unspecified"))
      (node (ref "USB1") (pin "B1A12") (pinfunction "GND_B1A12") (pintype "unspecified"))
      (node (ref "USB3") (pin "4") (pinfunction "GND_4") (pintype "input"))
      (node (ref "USB3") (pin "5") (pinfunction "EH_5") (pintype "unspecified"))
      (node (ref "USB8") (pin "4") (pinfunction "GND_4") (pintype "input"))
      (node (ref "USB8") (pin "5") (pinfunction "EH_5") (pintype "unspecified"))
      (node (ref "X1") (pin "2") (pinfunction "GND_2") (pintype "input"))
      (node (ref "X1") (pin "4") (pinfunction "GND_4") (pintype "input"))
    )
    (net (code "39") (name "Net-(BS-BS)") (class "Default")
      (node (ref "BS") (pin "1") (pinfunction "BS_1") (pintype "unspecified"))
      (node (ref "C55") (pin "2") (pinfunction "2_2") (pintype "unspecified"))
    )
    (net (code "40") (name "Net-(BS-FB)") (class "Default")
      (node (ref "BS") (pin "3") (pinfunction "FB_3") (pintype "unspecified"))
      (node (ref "C53") (pin "1") (pinfunction "1_1") (pintype "unspecified"))
      (node (ref "R17") (pin "2") (pinfunction "2_2") (pintype "unspecified"))
      (node (ref "R18") (pin "1") (pinfunction "1_1") (pintype "unspecified"))
    )
    (net (code "41") (name "Net-(BS-SW)") (class "Default")
      (node (ref "BS") (pin "6") (pinfunction "SW_6") (pintype "unspecified"))
      (node (ref "C55") (pin "1") (pinfunction "1_1") (pintype "unspecified"))
      (node (ref "L7") (pin "1") (pinfunction "1_1") (pintype "unspecified"))
    )
    (net (code "42") (name "Net-(C18-Pad1)") (class "Default")
      (node (ref "C18") (pin "1") (pinfunction "1_1") (pintype "unspecified"))
      (node (ref "L3") (pin "2") (pinfunction "2_2") (pintype "unspecified"))
      (node (ref "U4") (pin "2") (pinfunction "VDD3P3_2") (pintype "unspecified"))
      (node (ref "U4") (pin "3") (pinfunction "VDD3P3_3") (pintype "unspecified"))
    )
    (net (code "43") (name "Net-(C28-Pad1)") (class "Default")
      (node (ref "C28") (pin "1") (pinfunction "1_1") (pintype "unspecified"))
      (node (ref "R2") (pin "1") (pinfunction "1_1") (pintype "unspecified"))
    )
    (net (code "44") (name "Net-(C28-Pad2)") (class "Default")
      (node (ref "C28") (pin "2") (pinfunction "2_2") (pintype "unspecified"))
      (node (ref "C30") (pin "2") (pinfunction "2_2") (pintype "unspecified"))
      (node (ref "L1") (pin "1") (pinfunction "1_1") (pintype "unspecified"))
      (node (ref "U1") (pin "2") (pinfunction "SW_2") (pintype "unspecified"))
      (node (ref "U1") (pin "3") (pinfunction "SW_3") (pintype "unspecified"))
      (node (ref "U1") (pin "4") (pinfunction "SW_4") (pintype "unspecified"))
      (node (ref "U1") (pin "5") (pinfunction "SW_5") (pintype "unspecified"))
      (node (ref "U1") (pin "6") (pinfunction "SW_6") (pintype "unspecified"))
    )
    (net (code "45") (name "Net-(C37-Pad2)") (class "Default")
      (node (ref "C37") (pin "2") (pinfunction "2_2") (pintype "unspecified"))
      (node (ref "C39") (pin "2") (pinfunction "2_2") (pintype "unspecified"))
      (node (ref "L2") (pin "1") (pinfunction "1_1") (pintype "unspecified"))
      (node (ref "U2") (pin "2") (pinfunction "SW_2") (pintype "unspecified"))
      (node (ref "U2") (pin "3") (pinfunction "SW_3") (pintype "unspecified"))
      (node (ref "U2") (pin "4") (pinfunction "SW_4") (pintype "unspecified"))
      (node (ref "U2") (pin "5") (pinfunction "SW_5") (pintype "unspecified"))
      (node (ref "U2") (pin "6") (pinfunction "SW_6") (pintype "unspecified"))
    )
    (net (code "46") (name "Net-(C39-Pad1)") (class "Default")
      (node (ref "C39") (pin "1") (pinfunction "1_1") (pintype "unspecified"))
      (node (ref "R15") (pin "1") (pinfunction "1_1") (pintype "unspecified"))
    )
    (net (code "47") (name "Net-(C45-Pad2)") (class "Default")
      (node (ref "C45") (pin "2") (pinfunction "2_2") (pintype "unspecified"))
      (node (ref "R16") (pin "2") (pinfunction "2_2") (pintype "unspecified"))
    )
    (net (code "48") (name "Net-(C52-Pad2)") (class "Default")
      (node (ref "C52") (pin "2") (pinfunction "2_2") (pintype "unspecified"))
      (node (ref "R13") (pin "2") (pinfunction "2_2") (pintype "unspecified"))
    )
    (net (code "49") (name "Net-(C63-Pad1)") (class "Default")
      (node (ref "C63") (pin "1") (pinfunction "1_1") (pintype "unspecified"))
      (node (ref "R19") (pin "1") (pinfunction "1_1") (pintype "unspecified"))
    )
    (net (code "50") (name "Net-(DC2-Pad1)") (class "Default")
      (node (ref "DC2") (pin "1") (pinfunction "1_1") (pintype "unspecified"))
      (node (ref "U5") (pin "1") (pinfunction "1_1") (pintype "unspecified"))
    )
    (net (code "51") (name "Net-(LED1-DI)") (class "Default")
      (node (ref "LED1") (pin "3") (pinfunction "DI_3") (pintype "unspecified"))
      (node (ref "LED2") (pin "1") (pinfunction "DO_1") (pintype "unspecified"))
    )
    (net (code "52") (name "Net-(OLED1-BS1)") (class "Default")
      (node (ref "OLED1") (pin "11") (pinfunction "BS1_11") (pintype "passive"))
      (node (ref "R7") (pin "1") (pinfunction "1_1") (pintype "unspecified"))
    )
    (net (code "53") (name "Net-(OLED1-C1N)") (class "Default")
      (node (ref "C2") (pin "2") (pinfunction "2_2") (pintype "unspecified"))
      (node (ref "OLED1") (pin "5") (pinfunction "C1N_5") (pintype "passive"))
    )
    (net (code "54") (name "Net-(OLED1-C1P)") (class "Default")
      (node (ref "C2") (pin "1") (pinfunction "1_1") (pintype "unspecified"))
      (node (ref "OLED1") (pin "4") (pinfunction "C1P_4") (pintype "passive"))
    )
    (net (code "55") (name "Net-(OLED1-C2N)") (class "Default")
      (node (ref "C3") (pin "2") (pinfunction "2_2") (pintype "unspecified"))
      (node (ref "OLED1") (pin "3") (pinfunction "C2N_3") (pintype "passive"))
    )
    (net (code "56") (name "Net-(OLED1-C2P)") (class "Default")
      (node (ref "C3") (pin "1") (pinfunction "1_1") (pintype "unspecified"))
      (node (ref "OLED1") (pin "2") (pinfunction "C2P_2") (pintype "passive"))
    )
    (net (code "57") (name "Net-(OLED1-D{slash}C#)") (class "Default")
      (node (ref "OLED1") (pin "15") (pinfunction "D/C#_15") (pintype "passive"))
      (node (ref "R8") (pin "2") (pinfunction "2_2") (pintype "unspecified"))
      (node (ref "R9") (pin "1") (pinfunction "1_1") (pintype "unspecified"))
    )
    (net (code "58") (name "Net-(OLED1-IREF)") (class "Default")
      (node (ref "OLED1") (pin "26") (pinfunction "IREF_26") (pintype "passive"))
      (node (ref "R10") (pin "1") (pinfunction "1_1") (pintype "unspecified"))
    )
    (net (code "59") (name "Net-(OLED1-RES#)") (class "Default")
      (node (ref "C12") (pin "1") (pinfunction "1_1") (pintype "unspecified"))
      (node (ref "OLED1") (pin "14") (pinfunction "RES#_14") (pintype "passive"))
      (node (ref "R11") (pin "1") (pinfunction "1_1") (pintype "unspecified"))
      (node (ref "U6") (pin "2") (pinfunction "A_2") (pintype "unspecified"))
    )
    (net (code "60") (name "Net-(OLED1-VCC)") (class "Default")
      (node (ref "C10") (pin "1") (pinfunction "1_1") (pintype "unspecified"))
      (node (ref "OLED1") (pin "28") (pinfunction "VCC_28") (pintype "passive"))
    )
    (net (code "61") (name "Net-(OLED1-VCOMH)") (class "Default")
      (node (ref "C11") (pin "1") (pinfunction "1_1") (pintype "unspecified"))
      (node (ref "OLED1") (pin "27") (pinfunction "VCOMH_27") (pintype "passive"))
    )
    (net (code "62") (name "Net-(Q1-D)") (class "Default")
      (node (ref "C63") (pin "2") (pinfunction "2_2") (pintype "unspecified"))
      (node (ref "DC2") (pin "2") (pinfunction "2_2") (pintype "unspecified"))
      (node (ref "Q1") (pin "5") (pinfunction "D_5") (pintype "unspecified"))
    )
    (net (code "63") (name "Net-(Q1-G)") (class "Default")
      (node (ref "C64") (pin "2") (pinfunction "2_2") (pintype "unspecified"))
      (node (ref "D2") (pin "1") (pinfunction "1_1") (pintype "unspecified"))
      (node (ref "Q1") (pin "4") (pinfunction "G_4") (pintype "unspecified"))
      (node (ref "R20") (pin "1") (pinfunction "1_1") (pintype "unspecified"))
      (node (ref "R21") (pin "2") (pinfunction "2_2") (pintype "unspecified"))
    )
    (net (code "64") (name "Net-(Q2-D)") (class "Default")
      (node (ref "C22") (pin "2") (pinfunction "2_2") (pintype "unspecified"))
      (node (ref "C60") (pin "1") (pinfunction "1_1") (pintype "unspecified"))
      (node (ref "Q2") (pin "3") (pinfunction "D_3") (pintype "unspecified"))
      (node (ref "U3") (pin "7") (pinfunction "VIN_7") (pintype "unspecified"))
    )
    (net (code "65") (name "Net-(Q3-D)") (class "Default")
      (node (ref "C49") (pin "2") (pinfunction "2_2") (pintype "unspecified"))
      (node (ref "C59") (pin "1") (pinfunction "1_1") (pintype "unspecified"))
      (node (ref "Q3") (pin "3") (pinfunction "D_3") (pintype "unspecified"))
      (node (ref "U8") (pin "7") (pinfunction "VIN_7") (pintype "unspecified"))
    )
    (net (code "66") (name "Net-(Q4-B-Pad2)") (class "Default")
      (node (ref "Q4") (pin "2") (pinfunction "B_2") (pintype "unspecified"))
      (node (ref "R27") (pin "1") (pinfunction "1_1") (pintype "unspecified"))
    )
    (net (code "67") (name "Net-(Q4-B-Pad5)") (class "Default")
      (node (ref "Q4") (pin "5") (pinfunction "B_5") (pintype "unspecified"))
      (node (ref "R28") (pin "2") (pinfunction "2_2") (pintype "unspecified"))
    )
    (net (code "68") (name "Net-(U1-BST)") (class "Default")
      (node (ref "C30") (pin "1") (pinfunction "1_1") (pintype "unspecified"))
      (node (ref "U1") (pin "7") (pinfunction "BST_7") (pintype "unspecified"))
    )
    (net (code "69") (name "Net-(U1-PSET)") (class "Default")
      (node (ref "R5") (pin "1") (pinfunction "1_1") (pintype "unspecified"))
      (node (ref "U1") (pin "12") (pinfunction "PSET_12") (pintype "unspecified"))
    )
    (net (code "70") (name "Net-(U1-VDRV)") (class "Default")
      (node (ref "C31") (pin "2") (pinfunction "2_2") (pintype "unspecified"))
      (node (ref "U1") (pin "10") (pinfunction "VDRV_10") (pintype "unspecified"))
    )
    (net (code "71") (name "Net-(U2-BST)") (class "Default")
      (node (ref "C37") (pin "1") (pinfunction "1_1") (pintype "unspecified"))
      (node (ref "U2") (pin "7") (pinfunction "BST_7") (pintype "unspecified"))
    )
    (net (code "72") (name "Net-(U2-PSET)") (class "Default")
      (node (ref "R12") (pin "1") (pinfunction "1_1") (pintype "unspecified"))
      (node (ref "U2") (pin "12") (pinfunction "PSET_12") (pintype "unspecified"))
    )
    (net (code "73") (name "Net-(U2-VDRV)") (class "Default")
      (node (ref "C36") (pin "2") (pinfunction "2_2") (pintype "unspecified"))
      (node (ref "U2") (pin "10") (pinfunction "VDRV_10") (pintype "unspecified"))
    )
    (net (code "74") (name "Net-(U3-BST)") (class "Default")
      (node (ref "C47") (pin "1") (pinfunction "1_1") (pintype "unspecified"))
      (node (ref "U3") (pin "3") (pinfunction "BST_3") (pintype "unspecified"))
    )
    (net (code "75") (name "Net-(U3-SW)") (class "Default")
      (node (ref "C47") (pin "2") (pinfunction "2_2") (pintype "unspecified"))
      (node (ref "L6") (pin "2") (pinfunction "2_2") (pintype "unspecified"))
      (node (ref "R16") (pin "1") (pinfunction "1_1") (pintype "unspecified"))
      (node (ref "U3") (pin "2") (pinfunction "SW_2") (pintype "unspecified"))
    )
    (net (code "76") (name "Net-(U4-LNA)") (class "Default")
      (node (ref "L4") (pin "1") (pinfunction "1_1") (pintype "unspecified"))
      (node (ref "U4") (pin "1") (pinfunction "LNA_1") (pintype "unspecified"))
    )
    (net (code "77") (name "Net-(U4-XTAL_N)") (class "Default")
      (node (ref "C20") (pin "2") (pinfunction "2_2") (pintype "unspecified"))
      (node (ref "U4") (pin "29") (pinfunction "XTAL_N_29") (pintype "unspecified"))
      (node (ref "X1") (pin "3") (pinfunction "OSC2_3") (pintype "input"))
    )
    (net (code "78") (name "Net-(U4-XTAL_P)") (class "Default")
      (node (ref "C19") (pin "2") (pinfunction "2_2") (pintype "unspecified"))
      (node (ref "U4") (pin "30") (pinfunction "XTAL_P_30") (pintype "unspecified"))
      (node (ref "X1") (pin "1") (pinfunction "OSC1_1") (pintype "input"))
    )
    (net (code "79") (name "Net-(U8-BST)") (class "Default")
      (node (ref "C48") (pin "1") (pinfunction "1_1") (pintype "unspecified"))
      (node (ref "U8") (pin "3") (pinfunction "BST_3") (pintype "unspecified"))
    )
    (net (code "80") (name "Net-(U8-SW)") (class "Default")
      (node (ref "C48") (pin "2") (pinfunction "2_2") (pintype "unspecified"))
      (node (ref "L5") (pin "2") (pinfunction "2_2") (pintype "unspecified"))
      (node (ref "R13") (pin "1") (pinfunction "1_1") (pintype "unspecified"))
      (node (ref "U8") (pin "2") (pinfunction "SW_2") (pintype "unspecified"))
    )
    (net (code "81") (name "UC2-BUS") (class "Default")
      (node (ref "C38") (pin "2") (pinfunction "2_2") (pintype "unspecified"))
      (node (ref "H2") (pin "1") (pinfunction "1_1") (pintype "input"))
      (node (ref "H2") (pin "2") (pinfunction "2_2") (pintype "input"))
      (node (ref "H2") (pin "3") (pinfunction "3_3") (pintype "input"))
      (node (ref "R14") (pin "1") (pinfunction "1_1") (pintype "unspecified"))
      (node (ref "U2") (pin "24") (pinfunction "CSN_24") (pintype "unspecified"))
    )
    (net (code "82") (name "VBUS") (class "Default")
      (node (ref "BS") (pin "4") (pinfunction "EN_4") (pintype "unspecified"))
      (node (ref "BS") (pin "5") (pinfunction "IN_5") (pintype "unspecified"))
      (node (ref "C23") (pin "2") (pinfunction "2_2") (pintype "unspecified"))
      (node (ref "C32") (pin "2") (pinfunction "2_2") (pintype "unspecified"))
      (node (ref "C33") (pin "2") (pinfunction "2_2") (pintype "unspecified"))
      (node (ref "C35") (pin "2") (pinfunction "2_2") (pintype "unspecified"))
      (node (ref "C4") (pin "1") (pinfunction "1_1") (pintype "unspecified"))
      (node (ref "C57") (pin "1") (pinfunction "1_1") (pintype "unspecified"))
      (node (ref "C58") (pin "2") (pinfunction "2_2") (pintype "unspecified"))
      (node (ref "C61") (pin "1") (pinfunction "1_1") (pintype "unspecified"))
      (node (ref "C65") (pin "1") (pinfunction "1_1") (pintype "unspecified"))
      (node (ref "Q2") (pin "2") (pinfunction "S_2") (pintype "unspecified"))
      (node (ref "Q3") (pin "2") (pinfunction "S_2") (pintype "unspecified"))
      (node (ref "R20") (pin "2") (pinfunction "2_2") (pintype "unspecified"))
      (node (ref "R29") (pin "1") (pinfunction "1_1") (pintype "unspecified"))
      (node (ref "R30") (pin "1") (pinfunction "1_1") (pintype "unspecified"))
      (node (ref "U1") (pin "13") (pinfunction "VIN_13") (pintype "unspecified"))
      (node (ref "U1") (pin "14") (pinfunction "VIN_14") (pintype "unspecified"))
      (node (ref "U1") (pin "15") (pinfunction "VIN_15") (pintype "unspecified"))
      (node (ref "U1") (pin "16") (pinfunction "VIN_16") (pintype "unspecified"))
      (node (ref "U2") (pin "13") (pinfunction "VIN_13") (pintype "unspecified"))
      (node (ref "U2") (pin "14") (pinfunction "VIN_14") (pintype "unspecified"))
      (node (ref "U2") (pin "15") (pinfunction "VIN_15") (pintype "unspecified"))
      (node (ref "U2") (pin "16") (pinfunction "VIN_16") (pintype "unspecified"))
      (node (ref "U5") (pin "2") (pinfunction "2_2") (pintype "unspecified"))
    )
    (net (code "83") (name "VDD_SPI") (class "Default")
      (node (ref "C15") (pin "1") (pinfunction "1_1") (pintype "unspecified"))
      (node (ref "U4") (pin "18") (pinfunction "VDD_SPI_18") (pintype "unspecified"))
    )
    (net (code "84") (name "unconnected-(DC2-Pad3)") (class "Default")
      (node (ref "DC2") (pin "3") (pinfunction "3_3") (pintype "unspecified+no_connect"))
    )
    (net (code "85") (name "unconnected-(DC2-Pad4)") (class "Default")
      (node (ref "DC2") (pin "4") (pinfunction "4_4") (pintype "unspecified+no_connect"))
    )
    (net (code "86") (name "unconnected-(DC2-Pad5)") (class "Default")
      (node (ref "DC2") (pin "5") (pinfunction "5_5") (pintype "unspecified+no_connect"))
    )
    (net (code "87") (name "unconnected-(L4-Pad2)") (class "Default")
      (node (ref "L4") (pin "2") (pinfunction "2_2") (pintype "unspecified+no_connect"))
    )
    (net (code "88") (name "unconnected-(OLED1-NC-Pad7)") (class "Default")
      (node (ref "OLED1") (pin "7") (pinfunction "NC_7") (pintype "passive+no_connect"))
    )
    (net (code "89") (name "unconnected-(U1-GATE-Pad23)") (class "Default")
      (node (ref "U1") (pin "23") (pinfunction "GATE_23") (pintype "unspecified+no_connect"))
    )
    (net (code "90") (name "unconnected-(U1-NC-Pad17)") (class "Default")
      (node (ref "U1") (pin "17") (pinfunction "NC_17") (pintype "unspecified+no_connect"))
    )
    (net (code "91") (name "unconnected-(U1-VDD-Pad11)") (class "Default")
      (node (ref "U1") (pin "11") (pinfunction "VDD_11") (pintype "unspecified+no_connect"))
    )
    (net (code "92") (name "unconnected-(U2-GATE-Pad23)") (class "Default")
      (node (ref "U2") (pin "23") (pinfunction "GATE_23") (pintype "unspecified+no_connect"))
    )
    (net (code "93") (name "unconnected-(U2-NC-Pad17)") (class "Default")
      (node (ref "U2") (pin "17") (pinfunction "NC_17") (pintype "unspecified+no_connect"))
    )
    (net (code "94") (name "unconnected-(U2-VDD-Pad11)") (class "Default")
      (node (ref "U2") (pin "11") (pinfunction "VDD_11") (pintype "unspecified+no_connect"))
    )
    (net (code "95") (name "unconnected-(U3-HLED{slash}EN-Pad4)") (class "Default")
      (node (ref "U3") (pin "4") (pinfunction "HLED/EN_4") (pintype "unspecified+no_connect"))
    )
    (net (code "96") (name "unconnected-(U4-SPICLK-Pad22)") (class "Default")
      (node (ref "U4") (pin "22") (pinfunction "SPICLK_22") (pintype "unspecified+no_connect"))
    )
    (net (code "97") (name "unconnected-(U4-SPICS0-Pad21)") (class "Default")
      (node (ref "U4") (pin "21") (pinfunction "SPICS0_21") (pintype "unspecified+no_connect"))
    )
    (net (code "98") (name "unconnected-(U4-SPID-Pad23)") (class "Default")
      (node (ref "U4") (pin "23") (pinfunction "SPID_23") (pintype "unspecified+no_connect"))
    )
    (net (code "99") (name "unconnected-(U4-SPIHD-Pad19)") (class "Default")
      (node (ref "U4") (pin "19") (pinfunction "SPIHD_19") (pintype "unspecified+no_connect"))
    )
    (net (code "100") (name "unconnected-(U4-SPIQ-Pad24)") (class "Default")
      (node (ref "U4") (pin "24") (pinfunction "SPIQ_24") (pintype "unspecified+no_connect"))
    )
    (net (code "101") (name "unconnected-(U4-SPIWP-Pad20)") (class "Default")
      (node (ref "U4") (pin "20") (pinfunction "SPIWP_20") (pintype "unspecified+no_connect"))
    )
    (net (code "102") (name "unconnected-(U8-HLED{slash}EN-Pad4)") (class "Default")
      (node (ref "U8") (pin "4") (pinfunction "HLED/EN_4") (pintype "unspecified+no_connect"))
    )
    (net (code "103") (name "unconnected-(U9-ADC1-Pad16)") (class "Default")
      (node (ref "U9") (pin "16") (pinfunction "ADC1_16") (pintype "unspecified+no_connect"))
    )
    (net (code "104") (name "unconnected-(U9-ADC2-Pad15)") (class "Default")
      (node (ref "U9") (pin "15") (pinfunction "ADC2_15") (pintype "unspecified+no_connect"))
    )
    (net (code "105") (name "unconnected-(U9-ADC3-Pad13)") (class "Default")
      (node (ref "U9") (pin "13") (pinfunction "ADC3_13") (pintype "unspecified+no_connect"))
    )
    (net (code "106") (name "unconnected-(U9-INT1-Pad11)") (class "Default")
      (node (ref "U9") (pin "11") (pinfunction "INT1_11") (pintype "unspecified+no_connect"))
    )
    (net (code "107") (name "unconnected-(U9-INT2-Pad9)") (class "Default")
      (node (ref "U9") (pin "9") (pinfunction "INT2_9") (pintype "unspecified+no_connect"))
    )
    (net (code "108") (name "unconnected-(U9-NC-Pad2)") (class "Default")
      (node (ref "U9") (pin "2") (pinfunction "NC_2") (pintype "unspecified+no_connect"))
    )
    (net (code "109") (name "unconnected-(U9-NC-Pad3)") (class "Default")
      (node (ref "U9") (pin "3") (pinfunction "NC_3") (pintype "unspecified+no_connect"))
    )
    (net (code "110") (name "unconnected-(USB1-SBU1-PadA8)") (class "Default")
      (node (ref "USB1") (pin "A8") (pinfunction "SBU1_A8") (pintype "unspecified+no_connect"))
    )
    (net (code "111") (name "unconnected-(USB1-SBU2-PadB8)") (class "Default")
      (node (ref "USB1") (pin "B8") (pinfunction "SBU2_B8") (pintype "unspecified+no_connect"))
    )
  )
)
